# 2-Power.net
KiCad netlist of a schematic drawn in Altium Designer
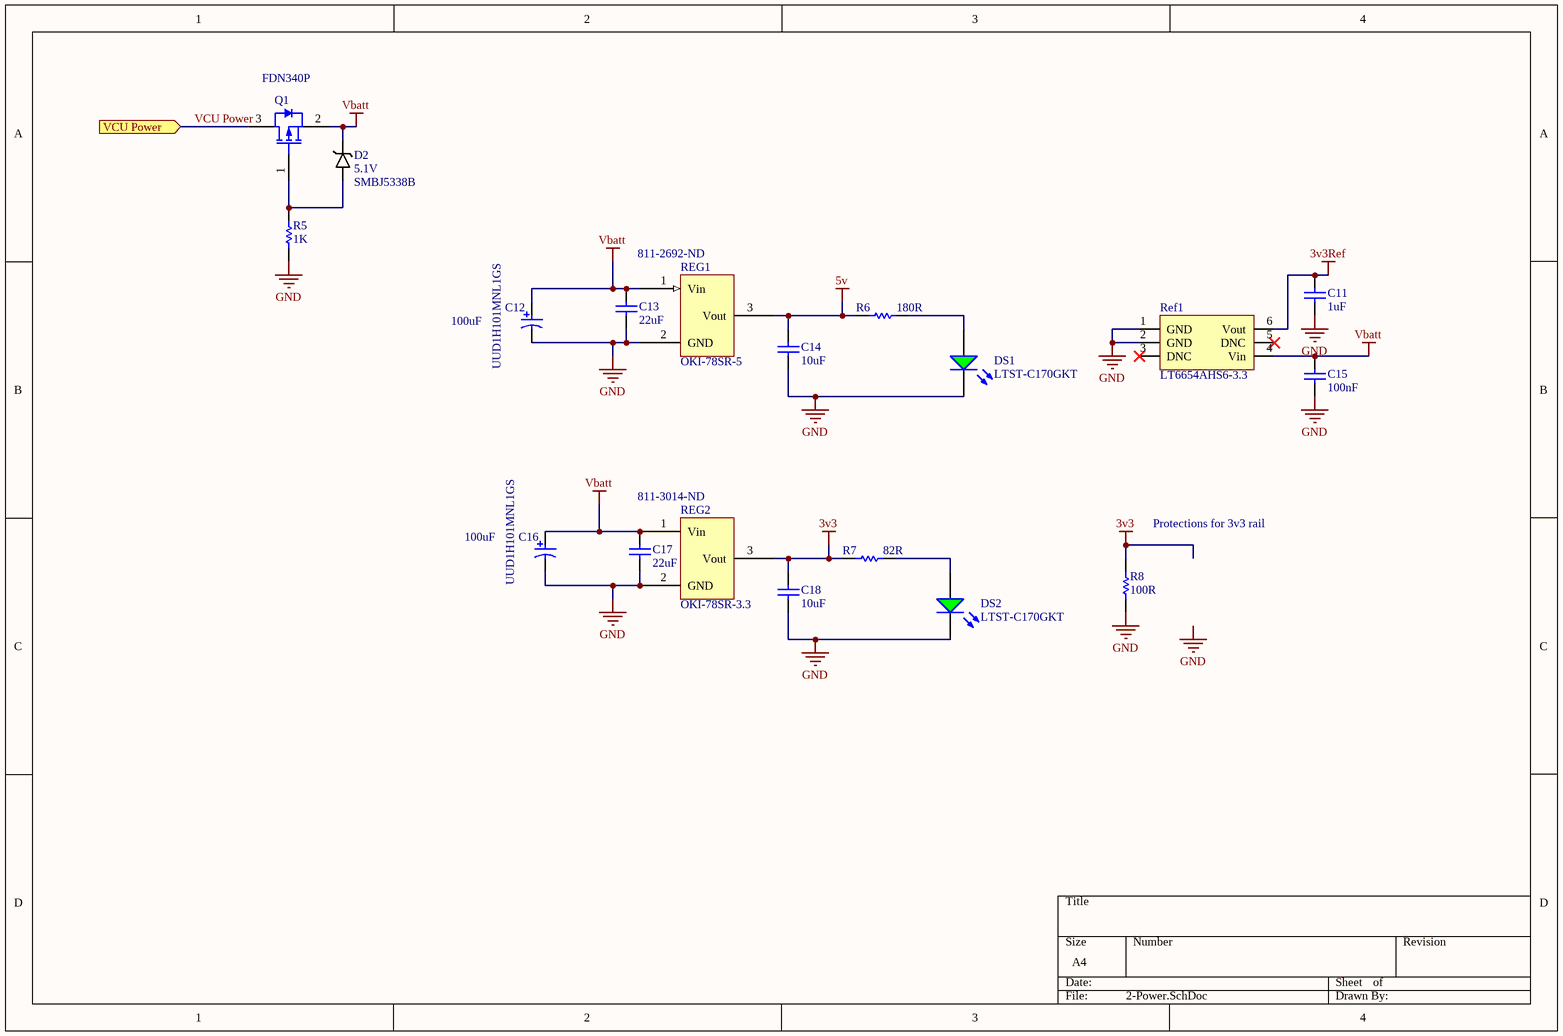
[diagram p0: 2-Power.SchDoc]

(export (version "E")
  (design (tool "Eeschema 10.0.6"))
  (components
    (comp (ref "C11")
      (value "1uF")
      (footprint "1608[0603]")
      (description "Capacitor")
      (fields
        (field (name "MANUFACTURER") "Murata Electronics North America")
        (field (name "MANUFACTURER PART NUMBER") "GRM188R61E105KA12D")
      )
      (libsource (lib "Miscellaneous Devices") (part "Cap"))
    )
    (comp (ref "C12")
      (value "UUD1H101MNL1GS")
      (footprint "NIC-CAPA2-8X10_V")
      (fields (field (name "MANUFACTURER") "Nichicon") (field (name "TOLERANCE") "±20%"))
      (libsource (lib "Altium Content Vault") (part "NIC-CAP-P-2"))
    )
    (comp (ref "C13")
      (value "22uF")
      (footprint "C1210_M")
      (description "Capacitor")
      (fields
        (field (name "MANUFACTURER") "Yageo")
        (field (name "MANUFACTURER PART NUMBER") "CC1210MKX5R8BB226")
      )
      (libsource (lib "Miscellaneous Devices") (part "Cap"))
    )
    (comp (ref "C14")
      (value "10uF")
      (footprint "C1210_M")
      (description "Capacitor")
      (fields
        (field (name "MANUFACTURER") "Yageo")
        (field (name "MANUFACTURER PART NUMBER") "CC1210ZKY5V8BB106")
      )
      (libsource (lib "Miscellaneous Devices") (part "Cap"))
    )
    (comp (ref "C15")
      (value "100nF")
      (footprint "1608[0603]")
      (description "Capacitor")
      (fields
        (field (name "MANUFACTURER") "Yageo")
        (field (name "MANUFACTURER PART NUMBER") "CC0603KRX7R9BB104")
      )
      (libsource (lib "Miscellaneous Devices") (part "Cap"))
    )
    (comp (ref "C16")
      (value "UUD1H101MNL1GS")
      (footprint "NIC-CAPA2-8X10_V")
      (fields (field (name "MANUFACTURER") "Nichicon") (field (name "TOLERANCE") "±20%"))
      (libsource (lib "Altium Content Vault") (part "NIC-CAP-P-2"))
    )
    (comp (ref "C17")
      (value "22uF")
      (footprint "C1210_M")
      (description "Capacitor")
      (fields
        (field (name "MANUFACTURER") "Yageo")
        (field (name "MANUFACTURER PART NUMBER") "CC1210MKX5R8BB226")
      )
      (libsource (lib "Miscellaneous Devices") (part "Cap"))
    )
    (comp (ref "C18")
      (value "10uF")
      (footprint "C1210_M")
      (description "Capacitor")
      (fields
        (field (name "MANUFACTURER") "Yageo")
        (field (name "MANUFACTURER PART NUMBER") "CC1210ZKY5V8BB106")
      )
      (libsource (lib "Miscellaneous Devices") (part "Cap"))
    )
    (comp (ref "D2")
      (value "Zener Diode, 5.1V, 5W SMBJ5338B")
      (footprint "DO-214AA (SMB)")
      (fields
        (field (name "POWER") "5W")
        (field (name "REVERSE VOLTAGE") "5.1V")
        (field (name "PART NUMBER") "SMBJ5338B")
      )
      (libsource (lib "VCU Library") (part "Zener Diode, 5.1V, 5W SMBJ5338B"))
    )
    (comp (ref "DS1")
      (value "LTST-C170GKT")
      (footprint "LTST-C170GKT_V")
      (description "LED Uni-Color Green, 100 mW, 120 mA, -55 to 85 degC, 2-Pin SMD, RoHS, Tape and Reel")
      (fields (field (name "MANUFACTURER") "Lite-On"))
      (libsource (lib "Altium Content Vault") (part "LED-GREEN-AK-2"))
    )
    (comp (ref "DS2")
      (value "LTST-C170GKT")
      (footprint "LTST-C170GKT_V")
      (description "LED Uni-Color Green, 100 mW, 120 mA, -55 to 85 degC, 2-Pin SMD, RoHS, Tape and Reel")
      (fields (field (name "MANUFACTURER") "Lite-On"))
      (libsource (lib "Altium Content Vault") (part "LED-GREEN-AK-2"))
    )
    (comp (ref "Q1")
      (value "FDN340P")
      (footprint "FAIR-SSOT3L-3_V")
      (fields (field (name "MANUFACTURER") "Fairchild Semiconductor"))
      (libsource (lib "Altium Content Vault") (part "PEMOS-GSD-3"))
    )
    (comp (ref "R5")
      (value "1K")
      (footprint "1608[0603]")
      (description "Resistor")
      (fields
        (field (name "MANUFACTURER") "Panasonic Electronic Components")
        (field (name "MANUFACTURER PART NUMBER") "ERJ-PA3F1001V")
      )
      (libsource (lib "Miscellaneous Devices") (part "Res1"))
    )
    (comp (ref "R6")
      (value "180R")
      (footprint "1608[0603]")
      (description "Resistor")
      (fields
        (field (name "MANUFACTURER") "Yageo")
        (field (name "MANUFACTURER PART NUMBER") "RC0603JR-07180RL")
      )
      (libsource (lib "Miscellaneous Devices") (part "Res1"))
    )
    (comp (ref "R7")
      (value "82R")
      (footprint "1608[0603]")
      (description "Resistor")
      (fields
        (field (name "MANUFACTURER") "Yageo")
        (field (name "MANUFACTURER PART NUMBER") "RC0603JR-0782RL")
      )
      (libsource (lib "Miscellaneous Devices") (part "Res1"))
    )
    (comp (ref "R8")
      (value "100R")
      (footprint "RESC1206(3216)_M")
      (description "100R 0.25W 5% 1206 (3216 Metric)  SMD")
      (fields (field (name "TOLERANCE") "5 %") (field (name "POWER") "0.25 W"))
      (libsource (lib "Altium Content Vault") (part "RES"))
    )
    (comp (ref "Ref1")
      (value "LT6654AHS6-3.3")
      (footprint "TSOT-23 S6")
      (fields
        (field (name "DIGIKEY PART NUMBER") "LT6654AHS6-3.3#TRMPBFCT-ND")
        (field (name "MANUFACTURER") "Linear Technology")
        (field (name "TOLERANCE") "±0.05%")
      )
      (libsource (lib "VCU Library") (part "LT6654AHS6-3.3"))
    )
    (comp (ref "REG1")
      (value "OKI-78SR-5")
      (footprint "Reg - TH, 3 pin, 100 mil Pitch, HTL")
      (fields
        (field (name "MANUFACTURER") "Murata Power Solutions Inc.")
        (field (name "MANUFACTURER PART NUMBER") "OKI-78SR-3.3/1.5-W36-C")
        (field (name "SUPPLIER PART NUMBER 2") "811-2692-ND")
      )
      (libsource (lib "FE Schem Lib") (part "OKI-78SR-5"))
    )
    (comp (ref "REG2")
      (value "OKI-78SR-3.3")
      (footprint "Reg - TH, 3 pin, 100 mil Pitch, VTL")
      (description "3.3V DCDC")
      (fields
        (field (name "SUPPLIER PART NUMBER 2") "811-3014-ND")
        (field (name "MANUFACTURER") "Murata Power Solutions Inc.")
        (field (name "MANUFACTURER PART NUMBER") "OKI-78SR-3.3/1.5-W36H-C")
      )
      (libsource (lib "") (part "OKI-78SR-5_1"))
    )
  )
  (nets
    (net (code "1") (name "/VCU Power") (class "Default")
      (node (ref "Q1") (pin "3") (pinfunction "DRAIN_3") (pintype "passive"))
    )
    (net (code "2") (name "3v3") (class "Default")
      (node (ref "C18") (pin "2") (pinfunction "2_2") (pintype "passive"))
      (node (ref "R7") (pin "1") (pinfunction "1_1") (pintype "passive"))
      (node (ref "R8") (pin "2") (pinfunction "2_2") (pintype "passive"))
      (node (ref "REG2") (pin "3") (pinfunction "Vout_3") (pintype "passive"))
    )
    (net (code "3") (name "3v3Ref") (class "Default")
      (node (ref "C11") (pin "2") (pinfunction "2_2") (pintype "passive"))
      (node (ref "Ref1") (pin "6") (pinfunction "Vout_6") (pintype "passive"))
    )
    (net (code "4") (name "5v") (class "Default")
      (node (ref "C14") (pin "2") (pinfunction "2_2") (pintype "passive"))
      (node (ref "R6") (pin "1") (pinfunction "1_1") (pintype "passive"))
      (node (ref "REG1") (pin "3") (pinfunction "Vout_3") (pintype "power_in"))
    )
    (net (code "5") (name "GND") (class "Default")
      (node (ref "C11") (pin "1") (pinfunction "1_1") (pintype "passive"))
      (node (ref "C12") (pin "2") (pinfunction "2_2") (pintype "passive"))
      (node (ref "C13") (pin "1") (pinfunction "1_1") (pintype "passive"))
      (node (ref "C14") (pin "1") (pinfunction "1_1") (pintype "passive"))
      (node (ref "C15") (pin "1") (pinfunction "1_1") (pintype "passive"))
      (node (ref "C16") (pin "2") (pinfunction "2_2") (pintype "passive"))
      (node (ref "C17") (pin "1") (pinfunction "1_1") (pintype "passive"))
      (node (ref "C18") (pin "1") (pinfunction "1_1") (pintype "passive"))
      (node (ref "DS1") (pin "2") (pinfunction "K_2") (pintype "passive"))
      (node (ref "DS2") (pin "2") (pinfunction "K_2") (pintype "passive"))
      (node (ref "R5") (pin "1") (pinfunction "1_1") (pintype "passive"))
      (node (ref "R8") (pin "1") (pinfunction "1_1") (pintype "passive"))
      (node (ref "REG1") (pin "2") (pinfunction "GND_2") (pintype "passive"))
      (node (ref "REG2") (pin "2") (pinfunction "GND_2") (pintype "passive"))
      (node (ref "Ref1") (pin "1") (pinfunction "GND_1") (pintype "passive"))
      (node (ref "Ref1") (pin "2") (pinfunction "GND_2") (pintype "passive"))
    )
    (net (code "6") (name "Net-(D2-2)") (class "Default")
      (node (ref "D2") (pin "A") (pinfunction "2_A") (pintype "passive"))
      (node (ref "Q1") (pin "1") (pinfunction "GATE_1") (pintype "passive"))
      (node (ref "R5") (pin "2") (pinfunction "2_2") (pintype "passive"))
    )
    (net (code "7") (name "Net-(DS1-A)") (class "Default")
      (node (ref "DS1") (pin "1") (pinfunction "A_1") (pintype "passive"))
      (node (ref "R6") (pin "2") (pinfunction "2_2") (pintype "passive"))
    )
    (net (code "8") (name "Net-(DS2-A)") (class "Default")
      (node (ref "DS2") (pin "1") (pinfunction "A_1") (pintype "passive"))
      (node (ref "R7") (pin "2") (pinfunction "2_2") (pintype "passive"))
    )
    (net (code "9") (name "Vbatt") (class "Default")
      (node (ref "C12") (pin "1") (pinfunction "1_1") (pintype "passive"))
      (node (ref "C13") (pin "2") (pinfunction "2_2") (pintype "passive"))
      (node (ref "C15") (pin "2") (pinfunction "2_2") (pintype "passive"))
      (node (ref "C16") (pin "1") (pinfunction "1_1") (pintype "passive"))
      (node (ref "C17") (pin "2") (pinfunction "2_2") (pintype "passive"))
      (node (ref "D2") (pin "K") (pinfunction "1_K") (pintype "passive"))
      (node (ref "Q1") (pin "2") (pinfunction "SOURCE_2") (pintype "passive"))
      (node (ref "REG1") (pin "1") (pinfunction "Vin_1") (pintype "input"))
      (node (ref "REG2") (pin "1") (pinfunction "Vin_1") (pintype "passive"))
      (node (ref "Ref1") (pin "4") (pinfunction "Vin_4") (pintype "passive"))
    )
    (net (code "10") (name "unconnected-(Ref1-DNC-Pad3)") (class "Default")
      (node (ref "Ref1") (pin "3") (pinfunction "DNC_3") (pintype "passive+no_connect"))
    )
    (net (code "11") (name "unconnected-(Ref1-DNC-Pad5)") (class "Default")
      (node (ref "Ref1") (pin "5") (pinfunction "DNC_5") (pintype "passive+no_connect"))
    )
  )
)
